# Micro_Rev1j.net
KiCad netlist of a schematic drawn in EAGLE
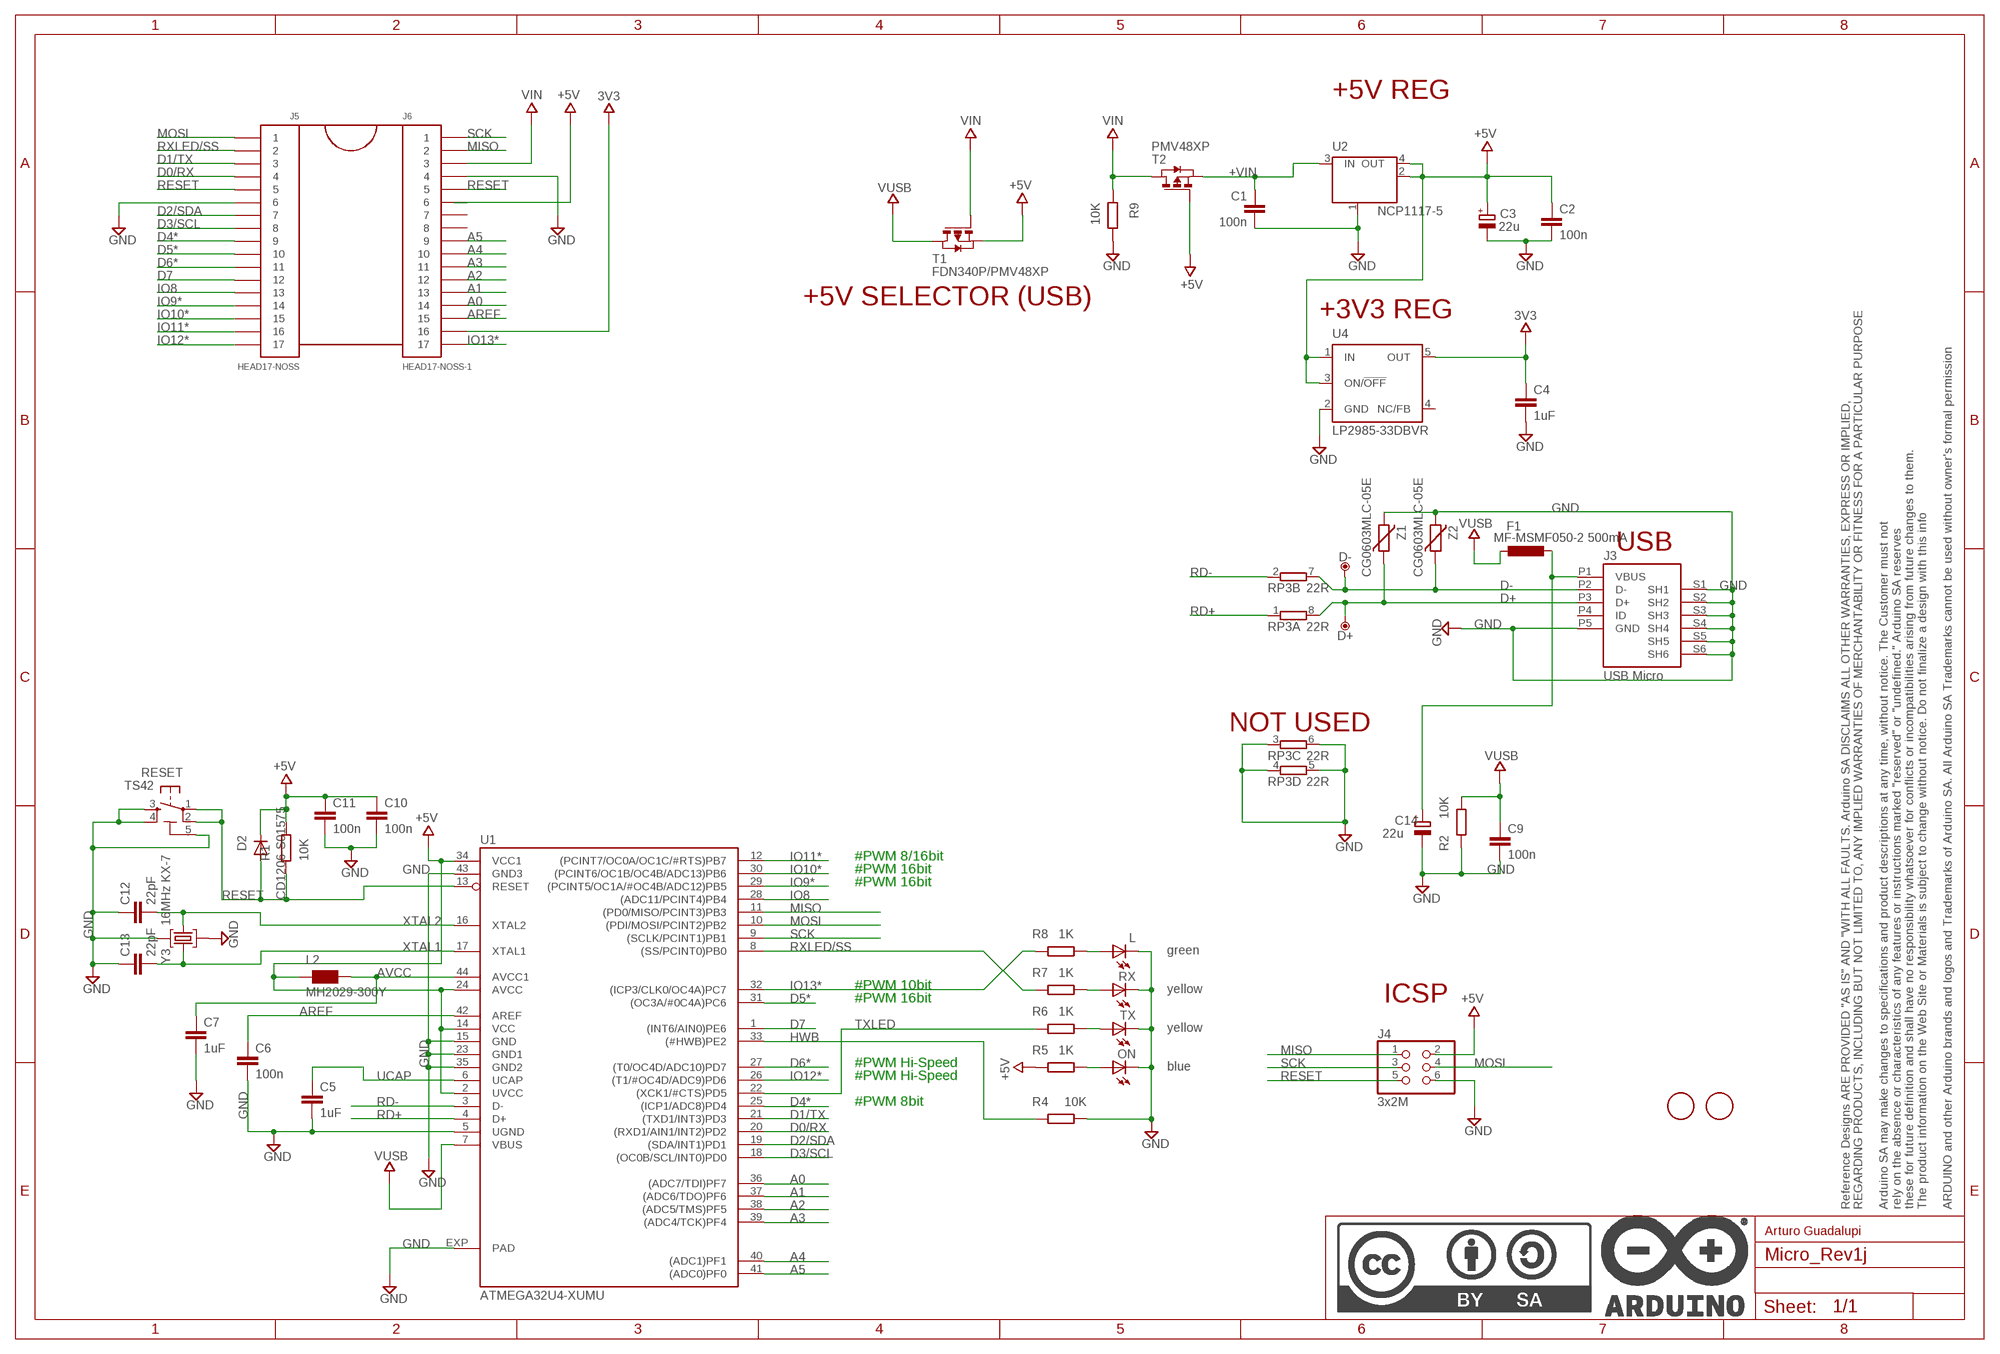
[diagram p0: schematic, sheet 1]

(export (version "E")
  (design (tool "Eeschema 10.0.6"))
  (components
    (comp (ref "C1")
      (value "100n")
      (footprint "eagle-import:C0402")
      (libsource (lib "eagle-import") (part "C-EUC0402"))
    )
    (comp (ref "C2")
      (value "100n")
      (footprint "eagle-import:C0402")
      (libsource (lib "eagle-import") (part "C-EUC0402"))
    )
    (comp (ref "C3")
      (value "22u")
      (footprint "eagle-import:SMC_B")
      (libsource (lib "eagle-import") (part "CPOL-EUSMCB"))
    )
    (comp (ref "C4")
      (value "1uF")
      (footprint "eagle-import:C0402")
      (libsource (lib "eagle-import") (part "C-EUC0402"))
    )
    (comp (ref "C5")
      (value "1uF")
      (footprint "eagle-import:C0402")
      (libsource (lib "eagle-import") (part "C-EUC0402"))
    )
    (comp (ref "C6")
      (value "100n")
      (footprint "eagle-import:C0402")
      (libsource (lib "eagle-import") (part "C-EUC0402"))
    )
    (comp (ref "C7")
      (value "1uF")
      (footprint "eagle-import:C0402")
      (libsource (lib "eagle-import") (part "C-EUC0402"))
    )
    (comp (ref "C9")
      (value "100n")
      (footprint "eagle-import:C0402")
      (libsource (lib "eagle-import") (part "C-EUC0402"))
    )
    (comp (ref "C10")
      (value "100n")
      (footprint "eagle-import:C0402")
      (libsource (lib "eagle-import") (part "C-EUC0402"))
    )
    (comp (ref "C11")
      (value "100n")
      (footprint "eagle-import:C0402")
      (libsource (lib "eagle-import") (part "C-EUC0402"))
    )
    (comp (ref "C12")
      (value "22pF")
      (footprint "eagle-import:C0402")
      (libsource (lib "eagle-import") (part "C-EUC0402"))
    )
    (comp (ref "C13")
      (value "22pF")
      (footprint "eagle-import:C0402")
      (libsource (lib "eagle-import") (part "C-EUC0402"))
    )
    (comp (ref "C14")
      (value "22u")
      (footprint "eagle-import:SMC_B")
      (libsource (lib "eagle-import") (part "CPOL-EUSMCB"))
    )
    (comp (ref "D+")
      (value "DNP")
      (footprint "eagle-import:TP-1.00MM")
      (libsource (lib "eagle-import") (part "TPTP-1.00MM"))
    )
    (comp (ref "D-")
      (value "DNP")
      (footprint "eagle-import:TP-1.00MM")
      (libsource (lib "eagle-import") (part "TPTP-1.00MM"))
    )
    (comp (ref "D2")
      (value "CD1206-S01575")
      (footprint "eagle-import:MINIMELF")
      (libsource (lib "eagle-import") (part "DIODE-MINIMELF"))
    )
    (comp (ref "F1")
      (value "MF-MSMF050-2 500mA")
      (footprint "eagle-import:L1812")
      (libsource (lib "eagle-import") (part "L-EUL1812"))
    )
    (comp (ref "FRAME1")
      (value "DNP")
      (footprint "eagle-import:FRAME")
      (libsource (lib "eagle-import") (part "A3-FRAME"))
    )
    (comp (ref "J3")
      (value "USB Micro")
      (footprint "eagle-import:CON2_USB_MICRO_B_AT")
      (fields (field (name "MANUFACTURER") "FCI"))
      (libsource (lib "eagle-import") (part "USB-MICRO-LEGACY"))
    )
    (comp (ref "J4")
      (value "3x2M")
      (footprint "eagle-import:2X03")
      (libsource (lib "eagle-import") (part "PINHD-2X3"))
    )
    (comp (ref "J5")
      (value "HEAD17-NOSS")
      (footprint "eagle-import:HEAD17-NOSS")
      (libsource (lib "eagle-import") (part "HEAD17-NOSS"))
    )
    (comp (ref "J6")
      (value "HEAD17-NOSS-1")
      (footprint "eagle-import:HEAD17-NOSS-1")
      (libsource (lib "eagle-import") (part "HEAD17-NOSS-1"))
    )
    (comp (ref "L")
      (value "green")
      (footprint "eagle-import:CHIPLED_0805")
      (libsource (lib "eagle-import") (part "LEDCHIPLED_0805"))
    )
    (comp (ref "L2")
      (value "MH2029-300Y")
      (footprint "eagle-import:0805")
      (libsource (lib "eagle-import") (part "WE-CBF_0805"))
    )
    (comp (ref "ON")
      (value "blue")
      (footprint "eagle-import:CHIPLED_0805")
      (libsource (lib "eagle-import") (part "LEDCHIPLED_0805"))
    )
    (comp (ref "R1")
      (value "10K")
      (footprint "eagle-import:R0402")
      (libsource (lib "eagle-import") (part "R-EU_R0402"))
    )
    (comp (ref "R2")
      (value "10K")
      (footprint "eagle-import:R0402")
      (libsource (lib "eagle-import") (part "R-EU_R0402"))
    )
    (comp (ref "R4")
      (value "10K")
      (footprint "eagle-import:R0402")
      (libsource (lib "eagle-import") (part "R-EU_R0402"))
    )
    (comp (ref "R5")
      (value "1K")
      (footprint "eagle-import:R0402")
      (libsource (lib "eagle-import") (part "R-EU_R0402"))
    )
    (comp (ref "R6")
      (value "1K")
      (footprint "eagle-import:R0402")
      (libsource (lib "eagle-import") (part "R-EU_R0402"))
    )
    (comp (ref "R7")
      (value "1K")
      (footprint "eagle-import:R0402")
      (libsource (lib "eagle-import") (part "R-EU_R0402"))
    )
    (comp (ref "R8")
      (value "1K")
      (footprint "eagle-import:R0402")
      (libsource (lib "eagle-import") (part "R-EU_R0402"))
    )
    (comp (ref "R9")
      (value "10K")
      (footprint "eagle-import:R0402")
      (libsource (lib "eagle-import") (part "R-EU_R0402"))
    )
    (comp (ref "RESET")
      (value "TS42")
      (footprint "eagle-import:TS42")
      (libsource (lib "eagle-import") (part "TS42"))
    )
    (comp (ref "RP3")
      (value "22R")
      (footprint "eagle-import:CAY16")
      (libsource (lib "eagle-import") (part "4R-NCAY16"))
    )
    (comp (ref "RX")
      (value "yellow")
      (footprint "eagle-import:CHIPLED_0805")
      (libsource (lib "eagle-import") (part "LEDCHIPLED_0805"))
    )
    (comp (ref "T1")
      (value "FDN340P/PMV48XP")
      (footprint "eagle-import:SOT-23")
      (libsource (lib "eagle-import") (part "PMOSSOT23"))
    )
    (comp (ref "T2")
      (value "PMV48XP")
      (footprint "eagle-import:SOT-23")
      (libsource (lib "eagle-import") (part "PMOSSOT23"))
    )
    (comp (ref "TX")
      (value "yellow")
      (footprint "eagle-import:CHIPLED_0805")
      (libsource (lib "eagle-import") (part "LEDCHIPLED_0805"))
    )
    (comp (ref "U$37")
      (value "DNP")
      (footprint "eagle-import:FD-1-1.5")
      (libsource (lib "eagle-import") (part "FIDUCIAL-1.5MM"))
    )
    (comp (ref "U$53")
      (value "DNP")
      (footprint "eagle-import:FD-1-1.5")
      (libsource (lib "eagle-import") (part "FIDUCIAL-1.5MM"))
    )
    (comp (ref "U1")
      (value "ATMEGA32U4-XUMU")
      (footprint "eagle-import:QFN44ML7X7")
      (libsource (lib "eagle-import") (part "ATMEGA32U4-XUMU"))
    )
    (comp (ref "U2")
      (value "NCP1117-5")
      (footprint "eagle-import:SOT223")
      (libsource (lib "eagle-import") (part "LINEAR_MC33269ST"))
    )
    (comp (ref "U4")
      (value "LP2985-33DBVR")
      (footprint "eagle-import:SOT23-DBV")
      (libsource (lib "eagle-import") (part "LP2985-XXDBVR33"))
    )
    (comp (ref "Y3")
      (value "16MHz KX-7")
      (footprint "eagle-import:CRYSTAL-3.2-2.5")
      (libsource (lib "eagle-import") (part "CRYSTAL-3.2-2.5"))
    )
    (comp (ref "Z1")
      (value "CG0603MLC-05E")
      (footprint "eagle-import:CT_CN0603")
      (libsource (lib "eagle-import") (part "VARISTORCN0603"))
    )
    (comp (ref "Z2")
      (value "CG0603MLC-05E")
      (footprint "eagle-import:CT_CN0603")
      (libsource (lib "eagle-import") (part "VARISTORCN0603"))
    )
  )
  (nets
    (net (code "1") (name "+5V") (class "Default")
      (node (ref "C10") (pin "1") (pinfunction "1_1") (pintype "passive"))
      (node (ref "C11") (pin "1") (pinfunction "1_1") (pintype "passive"))
      (node (ref "C2") (pin "1") (pinfunction "1_1") (pintype "passive"))
      (node (ref "C3") (pin "+") (pinfunction "+_+") (pintype "passive"))
      (node (ref "D2") (pin "C") (pinfunction "C_C") (pintype "passive"))
      (node (ref "J4") (pin "2") (pinfunction "2_2") (pintype "passive"))
      (node (ref "J6") (pin "6") (pinfunction "6_6") (pintype "passive"))
      (node (ref "L2") (pin "1") (pinfunction "1_1") (pintype "passive"))
      (node (ref "R1") (pin "1") (pinfunction "1_1") (pintype "passive"))
      (node (ref "R5") (pin "1") (pinfunction "1_1") (pintype "passive"))
      (node (ref "T1") (pin "2") (pinfunction "S_2") (pintype "passive"))
      (node (ref "T2") (pin "3") (pinfunction "G_3") (pintype "passive"))
      (node (ref "U1") (pin "14") (pinfunction "VCC_14") (pintype "power_in"))
      (node (ref "U1") (pin "2") (pinfunction "UVCC_2") (pintype "power_in"))
      (node (ref "U1") (pin "24") (pinfunction "AVCC_24") (pintype "power_in"))
      (node (ref "U1") (pin "34") (pinfunction "VCC1_34") (pintype "power_in"))
      (node (ref "U2") (pin "2") (pinfunction "OUT_2") (pintype "passive"))
      (node (ref "U2") (pin "4") (pinfunction "OUT_4") (pintype "passive"))
      (node (ref "U4") (pin "1") (pinfunction "IN_1") (pintype "input"))
      (node (ref "U4") (pin "3") (pinfunction "ON/~{OFF}_3") (pintype "input"))
    )
    (net (code "2") (name "/+VIN") (class "Default")
      (node (ref "C1") (pin "1") (pinfunction "1_1") (pintype "passive"))
      (node (ref "T2") (pin "2") (pinfunction "S_2") (pintype "passive"))
      (node (ref "U2") (pin "3") (pinfunction "IN_3") (pintype "input"))
    )
    (net (code "3") (name "/A0") (class "Default")
      (node (ref "J6") (pin "14") (pinfunction "14_14") (pintype "passive"))
      (node (ref "U1") (pin "36") (pinfunction "(ADC7/TDI)PF7_36") (pintype "bidirectional"))
    )
    (net (code "4") (name "/A1") (class "Default")
      (node (ref "J6") (pin "13") (pinfunction "13_13") (pintype "passive"))
      (node (ref "U1") (pin "37") (pinfunction "(ADC6/TDO)PF6_37") (pintype "bidirectional"))
    )
    (net (code "5") (name "/A2") (class "Default")
      (node (ref "J6") (pin "12") (pinfunction "12_12") (pintype "passive"))
      (node (ref "U1") (pin "38") (pinfunction "(ADC5/TMS)PF5_38") (pintype "bidirectional"))
    )
    (net (code "6") (name "/A3") (class "Default")
      (node (ref "J6") (pin "11") (pinfunction "11_11") (pintype "passive"))
      (node (ref "U1") (pin "39") (pinfunction "(ADC4/TCK)PF4_39") (pintype "bidirectional"))
    )
    (net (code "7") (name "/A4") (class "Default")
      (node (ref "J6") (pin "10") (pinfunction "10_10") (pintype "passive"))
      (node (ref "U1") (pin "40") (pinfunction "(ADC1)PF1_40") (pintype "bidirectional"))
    )
    (net (code "8") (name "/A5") (class "Default")
      (node (ref "J6") (pin "9") (pinfunction "9_9") (pintype "passive"))
      (node (ref "U1") (pin "41") (pinfunction "(ADC0)PF0_41") (pintype "bidirectional"))
    )
    (net (code "9") (name "/AREF") (class "Default")
      (node (ref "C6") (pin "1") (pinfunction "1_1") (pintype "passive"))
      (node (ref "J6") (pin "15") (pinfunction "15_15") (pintype "passive"))
      (node (ref "U1") (pin "42") (pinfunction "AREF_42") (pintype "power_in"))
    )
    (net (code "10") (name "/AVCC") (class "Default")
      (node (ref "C7") (pin "1") (pinfunction "1_1") (pintype "passive"))
      (node (ref "L2") (pin "2") (pinfunction "2_2") (pintype "passive"))
      (node (ref "U1") (pin "44") (pinfunction "AVCC1_44") (pintype "power_in"))
    )
    (net (code "11") (name "/D+") (class "Default")
      (node (ref "D+") (pin "X") (pinfunction "P$1_X") (pintype "passive"))
      (node (ref "J3") (pin "P3") (pinfunction "D+_P3") (pintype "bidirectional"))
      (node (ref "RP3") (pin "8") (pinfunction "2_8") (pintype "passive"))
      (node (ref "Z1") (pin "1") (pinfunction "1_1") (pintype "passive"))
    )
    (net (code "12") (name "/D-") (class "Default")
      (node (ref "D-") (pin "X") (pinfunction "P$1_X") (pintype "passive"))
      (node (ref "J3") (pin "P2") (pinfunction "D-_P2") (pintype "bidirectional"))
      (node (ref "RP3") (pin "7") (pinfunction "2_7") (pintype "passive"))
      (node (ref "Z2") (pin "1") (pinfunction "1_1") (pintype "passive"))
    )
    (net (code "13") (name "/D0{slash}RX") (class "Default")
      (node (ref "J5") (pin "4") (pinfunction "4_4") (pintype "passive"))
      (node (ref "U1") (pin "20") (pinfunction "(RXD1/AIN1/INT2)PD2_20") (pintype "bidirectional"))
    )
    (net (code "14") (name "/D1{slash}TX") (class "Default")
      (node (ref "J5") (pin "3") (pinfunction "3_3") (pintype "passive"))
      (node (ref "U1") (pin "21") (pinfunction "(TXD1/INT3)PD3_21") (pintype "bidirectional"))
    )
    (net (code "15") (name "/D2{slash}SDA") (class "Default")
      (node (ref "J5") (pin "7") (pinfunction "7_7") (pintype "passive"))
      (node (ref "U1") (pin "19") (pinfunction "(SDA/INT1)PD1_19") (pintype "bidirectional"))
    )
    (net (code "16") (name "/D3{slash}SCL") (class "Default")
      (node (ref "J5") (pin "8") (pinfunction "8_8") (pintype "passive"))
      (node (ref "U1") (pin "18") (pinfunction "(OC0B/SCL/INT0)PD0_18") (pintype "bidirectional"))
    )
    (net (code "17") (name "/D4*") (class "Default")
      (node (ref "J5") (pin "9") (pinfunction "9_9") (pintype "passive"))
      (node (ref "U1") (pin "25") (pinfunction "(ICP1/ADC8)PD4_25") (pintype "bidirectional"))
    )
    (net (code "18") (name "/D5*") (class "Default")
      (node (ref "J5") (pin "10") (pinfunction "10_10") (pintype "passive"))
      (node (ref "U1") (pin "31") (pinfunction "(OC3A/#0C4A)PC6_31") (pintype "bidirectional"))
    )
    (net (code "19") (name "/D6*") (class "Default")
      (node (ref "J5") (pin "11") (pinfunction "11_11") (pintype "passive"))
      (node (ref "U1") (pin "27") (pinfunction "(T0/OC4D/ADC10)PD7_27") (pintype "bidirectional"))
    )
    (net (code "20") (name "/D7") (class "Default")
      (node (ref "J5") (pin "12") (pinfunction "12_12") (pintype "passive"))
      (node (ref "U1") (pin "1") (pinfunction "(INT6/AIN0)PE6_1") (pintype "bidirectional"))
    )
    (net (code "21") (name "/HWB") (class "Default")
      (node (ref "R4") (pin "1") (pinfunction "1_1") (pintype "passive"))
      (node (ref "U1") (pin "33") (pinfunction "(#HWB)PE2_33") (pintype "bidirectional"))
    )
    (net (code "22") (name "/IO8") (class "Default")
      (node (ref "J5") (pin "13") (pinfunction "13_13") (pintype "passive"))
      (node (ref "U1") (pin "28") (pinfunction "(ADC11/PCINT4)PB4_28") (pintype "bidirectional"))
    )
    (net (code "23") (name "/IO9*") (class "Default")
      (node (ref "J5") (pin "14") (pinfunction "14_14") (pintype "passive"))
      (node (ref "U1") (pin "29") (pinfunction "(PCINT5/OC1A/#OC4B/ADC12)PB5_29") (pintype "bidirectional"))
    )
    (net (code "24") (name "/IO10*") (class "Default")
      (node (ref "J5") (pin "15") (pinfunction "15_15") (pintype "passive"))
      (node (ref "U1") (pin "30") (pinfunction "(PCINT6/OC1B/OC4B/ADC13)PB6_30") (pintype "bidirectional"))
    )
    (net (code "25") (name "/IO11*") (class "Default")
      (node (ref "J5") (pin "16") (pinfunction "16_16") (pintype "passive"))
      (node (ref "U1") (pin "12") (pinfunction "(PCINT7/OC0A/OC1C/#RTS)PB7_12") (pintype "bidirectional"))
    )
    (net (code "26") (name "/IO12*") (class "Default")
      (node (ref "J5") (pin "17") (pinfunction "17_17") (pintype "passive"))
      (node (ref "U1") (pin "26") (pinfunction "(T1/#OC4D/ADC9)PD6_26") (pintype "bidirectional"))
    )
    (net (code "27") (name "/IO13*") (class "Default")
      (node (ref "J6") (pin "17") (pinfunction "17_17") (pintype "passive"))
      (node (ref "R8") (pin "1") (pinfunction "1_1") (pintype "passive"))
      (node (ref "U1") (pin "32") (pinfunction "(ICP3/CLK0/OC4A)PC7_32") (pintype "bidirectional"))
    )
    (net (code "28") (name "/MISO") (class "Default")
      (node (ref "J4") (pin "1") (pinfunction "1_1") (pintype "passive"))
      (node (ref "J6") (pin "2") (pinfunction "2_2") (pintype "passive"))
      (node (ref "U1") (pin "11") (pinfunction "(PD0/MISO/PCINT3)PB3_11") (pintype "bidirectional"))
    )
    (net (code "29") (name "/MOSI") (class "Default")
      (node (ref "J4") (pin "4") (pinfunction "4_4") (pintype "passive"))
      (node (ref "J5") (pin "1") (pinfunction "1_1") (pintype "passive"))
      (node (ref "U1") (pin "10") (pinfunction "(PDI/MOSI/PCINT2)PB2_10") (pintype "bidirectional"))
    )
    (net (code "30") (name "/RD+") (class "Default")
      (node (ref "RP3") (pin "1") (pinfunction "1_1") (pintype "passive"))
      (node (ref "U1") (pin "4") (pinfunction "D+_4") (pintype "bidirectional"))
    )
    (net (code "31") (name "/RD-") (class "Default")
      (node (ref "RP3") (pin "2") (pinfunction "1_2") (pintype "passive"))
      (node (ref "U1") (pin "3") (pinfunction "D-_3") (pintype "bidirectional"))
    )
    (net (code "32") (name "/RESET") (class "Default")
      (node (ref "D2") (pin "A") (pinfunction "A_A") (pintype "passive"))
      (node (ref "J4") (pin "5") (pinfunction "5_5") (pintype "passive"))
      (node (ref "J5") (pin "5") (pinfunction "5_5") (pintype "passive"))
      (node (ref "J6") (pin "5") (pinfunction "5_5") (pintype "passive"))
      (node (ref "R1") (pin "2") (pinfunction "2_2") (pintype "passive"))
      (node (ref "RESET") (pin "1") (pinfunction "1_1") (pintype "passive"))
      (node (ref "RESET") (pin "2") (pinfunction "2_2") (pintype "passive"))
      (node (ref "U1") (pin "13") (pinfunction "RESET_13") (pintype "input"))
    )
    (net (code "33") (name "/RXLED{slash}SS") (class "Default")
      (node (ref "J5") (pin "2") (pinfunction "2_2") (pintype "passive"))
      (node (ref "R7") (pin "1") (pinfunction "1_1") (pintype "passive"))
      (node (ref "U1") (pin "8") (pinfunction "(SS/PCINT0)PB0_8") (pintype "bidirectional"))
    )
    (net (code "34") (name "/SCK") (class "Default")
      (node (ref "J4") (pin "3") (pinfunction "3_3") (pintype "passive"))
      (node (ref "J6") (pin "1") (pinfunction "1_1") (pintype "passive"))
      (node (ref "U1") (pin "9") (pinfunction "(SCLK/PCINT1)PB1_9") (pintype "bidirectional"))
    )
    (net (code "35") (name "/TXLED") (class "Default")
      (node (ref "R6") (pin "1") (pinfunction "1_1") (pintype "passive"))
      (node (ref "U1") (pin "22") (pinfunction "(XCK1/#CTS)PD5_22") (pintype "bidirectional"))
    )
    (net (code "36") (name "/UCAP") (class "Default")
      (node (ref "C5") (pin "1") (pinfunction "1_1") (pintype "passive"))
      (node (ref "U1") (pin "6") (pinfunction "UCAP_6") (pintype "passive"))
    )
    (net (code "37") (name "/XTAL1") (class "Default")
      (node (ref "C13") (pin "2") (pinfunction "2_2") (pintype "passive"))
      (node (ref "U1") (pin "17") (pinfunction "XTAL1_17") (pintype "bidirectional"))
      (node (ref "Y3") (pin "3") (pinfunction "C2_3") (pintype "passive"))
    )
    (net (code "38") (name "/XTAL2") (class "Default")
      (node (ref "C12") (pin "2") (pinfunction "2_2") (pintype "passive"))
      (node (ref "U1") (pin "16") (pinfunction "XTAL2_16") (pintype "bidirectional"))
      (node (ref "Y3") (pin "1") (pinfunction "C1_1") (pintype "passive"))
    )
    (net (code "39") (name "3V3") (class "Default")
      (node (ref "C4") (pin "1") (pinfunction "1_1") (pintype "passive"))
      (node (ref "J6") (pin "16") (pinfunction "16_16") (pintype "passive"))
      (node (ref "U4") (pin "5") (pinfunction "OUT_5") (pintype "passive"))
    )
    (net (code "40") (name "GND") (class "Default")
      (node (ref "C1") (pin "2") (pinfunction "2_2") (pintype "passive"))
      (node (ref "C10") (pin "2") (pinfunction "2_2") (pintype "passive"))
      (node (ref "C11") (pin "2") (pinfunction "2_2") (pintype "passive"))
      (node (ref "C12") (pin "1") (pinfunction "1_1") (pintype "passive"))
      (node (ref "C13") (pin "1") (pinfunction "1_1") (pintype "passive"))
      (node (ref "C14") (pin "-") (pinfunction "-_-") (pintype "passive"))
      (node (ref "C2") (pin "2") (pinfunction "2_2") (pintype "passive"))
      (node (ref "C3") (pin "-") (pinfunction "-_-") (pintype "passive"))
      (node (ref "C4") (pin "2") (pinfunction "2_2") (pintype "passive"))
      (node (ref "C5") (pin "2") (pinfunction "2_2") (pintype "passive"))
      (node (ref "C6") (pin "2") (pinfunction "2_2") (pintype "passive"))
      (node (ref "C7") (pin "2") (pinfunction "2_2") (pintype "passive"))
      (node (ref "C9") (pin "2") (pinfunction "2_2") (pintype "passive"))
      (node (ref "J3") (pin "P5") (pinfunction "GND_P5") (pintype "passive"))
      (node (ref "J3") (pin "S1") (pinfunction "SH1_S1") (pintype "passive"))
      (node (ref "J3") (pin "S2") (pinfunction "SH2_S2") (pintype "passive"))
      (node (ref "J3") (pin "S3") (pinfunction "SH3_S3") (pintype "passive"))
      (node (ref "J3") (pin "S4") (pinfunction "SH4_S4") (pintype "passive"))
      (node (ref "J3") (pin "S5") (pinfunction "SH5_S5") (pintype "passive"))
      (node (ref "J3") (pin "S6") (pinfunction "SH6_S6") (pintype "passive"))
      (node (ref "J4") (pin "6") (pinfunction "6_6") (pintype "passive"))
      (node (ref "J5") (pin "6") (pinfunction "6_6") (pintype "passive"))
      (node (ref "J6") (pin "4") (pinfunction "4_4") (pintype "passive"))
      (node (ref "L") (pin "C") (pinfunction "C_C") (pintype "passive"))
      (node (ref "ON") (pin "C") (pinfunction "C_C") (pintype "passive"))
      (node (ref "R2") (pin "1") (pinfunction "1_1") (pintype "passive"))
      (node (ref "R4") (pin "2") (pinfunction "2_2") (pintype "passive"))
      (node (ref "R9") (pin "1") (pinfunction "1_1") (pintype "passive"))
      (node (ref "RESET") (pin "3") (pinfunction "3_3") (pintype "passive"))
      (node (ref "RESET") (pin "4") (pinfunction "4_4") (pintype "passive"))
      (node (ref "RESET") (pin "5") (pinfunction "5-GND_5") (pintype "power_in"))
      (node (ref "RP3") (pin "3") (pinfunction "1_3") (pintype "passive"))
      (node (ref "RP3") (pin "4") (pinfunction "1_4") (pintype "passive"))
      (node (ref "RP3") (pin "5") (pinfunction "2_5") (pintype "passive"))
      (node (ref "RP3") (pin "6") (pinfunction "2_6") (pintype "passive"))
      (node (ref "RX") (pin "C") (pinfunction "C_C") (pintype "passive"))
      (node (ref "TX") (pin "C") (pinfunction "C_C") (pintype "passive"))
      (node (ref "U1") (pin "15") (pinfunction "GND_15") (pintype "power_in"))
      (node (ref "U1") (pin "23") (pinfunction "GND1_23") (pintype "power_in"))
      (node (ref "U1") (pin "35") (pinfunction "GND2_35") (pintype "power_in"))
      (node (ref "U1") (pin "43") (pinfunction "GND3_43") (pintype "power_in"))
      (node (ref "U1") (pin "5") (pinfunction "UGND_5") (pintype "power_in"))
      (node (ref "U1") (pin "EXP") (pinfunction "PAD_EXP") (pintype "power_in"))
      (node (ref "U2") (pin "1") (pinfunction "GND/ADJ_1") (pintype "input"))
      (node (ref "U4") (pin "2") (pinfunction "GND_2") (pintype "power_in"))
      (node (ref "Y3") (pin "2") (pinfunction "GND_2") (pintype "passive"))
      (node (ref "Y3") (pin "4") (pinfunction "GND_4") (pintype "passive"))
      (node (ref "Z1") (pin "2") (pinfunction "2_2") (pintype "passive"))
      (node (ref "Z2") (pin "2") (pinfunction "2_2") (pintype "passive"))
    )
    (net (code "41") (name "Net-(J3-VBUS)") (class "Default")
      (node (ref "C14") (pin "+") (pinfunction "+_+") (pintype "passive"))
      (node (ref "F1") (pin "1") (pinfunction "1_1") (pintype "passive"))
      (node (ref "J3") (pin "P1") (pinfunction "VBUS_P1") (pintype "power_in"))
    )
    (net (code "42") (name "Net-(L-PadA)") (class "Default")
      (node (ref "L") (pin "A") (pinfunction "A_A") (pintype "passive"))
      (node (ref "R8") (pin "2") (pinfunction "2_2") (pintype "passive"))
    )
    (net (code "43") (name "Net-(ON-PadA)") (class "Default")
      (node (ref "ON") (pin "A") (pinfunction "A_A") (pintype "passive"))
      (node (ref "R5") (pin "2") (pinfunction "2_2") (pintype "passive"))
    )
    (net (code "44") (name "Net-(R6-Pad2)") (class "Default")
      (node (ref "R6") (pin "2") (pinfunction "2_2") (pintype "passive"))
      (node (ref "TX") (pin "A") (pinfunction "A_A") (pintype "passive"))
    )
    (net (code "45") (name "Net-(R7-Pad2)") (class "Default")
      (node (ref "R7") (pin "2") (pinfunction "2_2") (pintype "passive"))
      (node (ref "RX") (pin "A") (pinfunction "A_A") (pintype "passive"))
    )
    (net (code "46") (name "VIN") (class "Default")
      (node (ref "J6") (pin "3") (pinfunction "3_3") (pintype "passive"))
      (node (ref "R9") (pin "2") (pinfunction "2_2") (pintype "passive"))
      (node (ref "T1") (pin "3") (pinfunction "G_3") (pintype "passive"))
      (node (ref "T2") (pin "1") (pinfunction "D_1") (pintype "passive"))
    )
    (net (code "47") (name "VUSB") (class "Default")
      (node (ref "C9") (pin "1") (pinfunction "1_1") (pintype "passive"))
      (node (ref "F1") (pin "2") (pinfunction "2_2") (pintype "passive"))
      (node (ref "R2") (pin "2") (pinfunction "2_2") (pintype "passive"))
      (node (ref "T1") (pin "1") (pinfunction "D_1") (pintype "passive"))
      (node (ref "U1") (pin "7") (pinfunction "VBUS_7") (pintype "input"))
    )
    (net (code "48") (name "unconnected-(J3-ID-PadP4)") (class "Default")
      (node (ref "J3") (pin "P4") (pinfunction "ID_P4") (pintype "bidirectional"))
    )
    (net (code "49") (name "unconnected-(J6-Pad7)") (class "Default")
      (node (ref "J6") (pin "7") (pinfunction "7_7") (pintype "passive"))
    )
    (net (code "50") (name "unconnected-(J6-Pad8)") (class "Default")
      (node (ref "J6") (pin "8") (pinfunction "8_8") (pintype "passive"))
    )
    (net (code "51") (name "unconnected-(U4-NC{slash}FB-Pad4)") (class "Default")
      (node (ref "U4") (pin "4") (pinfunction "NC/FB_4") (pintype "passive"))
    )
  )
)
